# ISP1507.net
KiCad netlist of a schematic drawn in Altium Designer
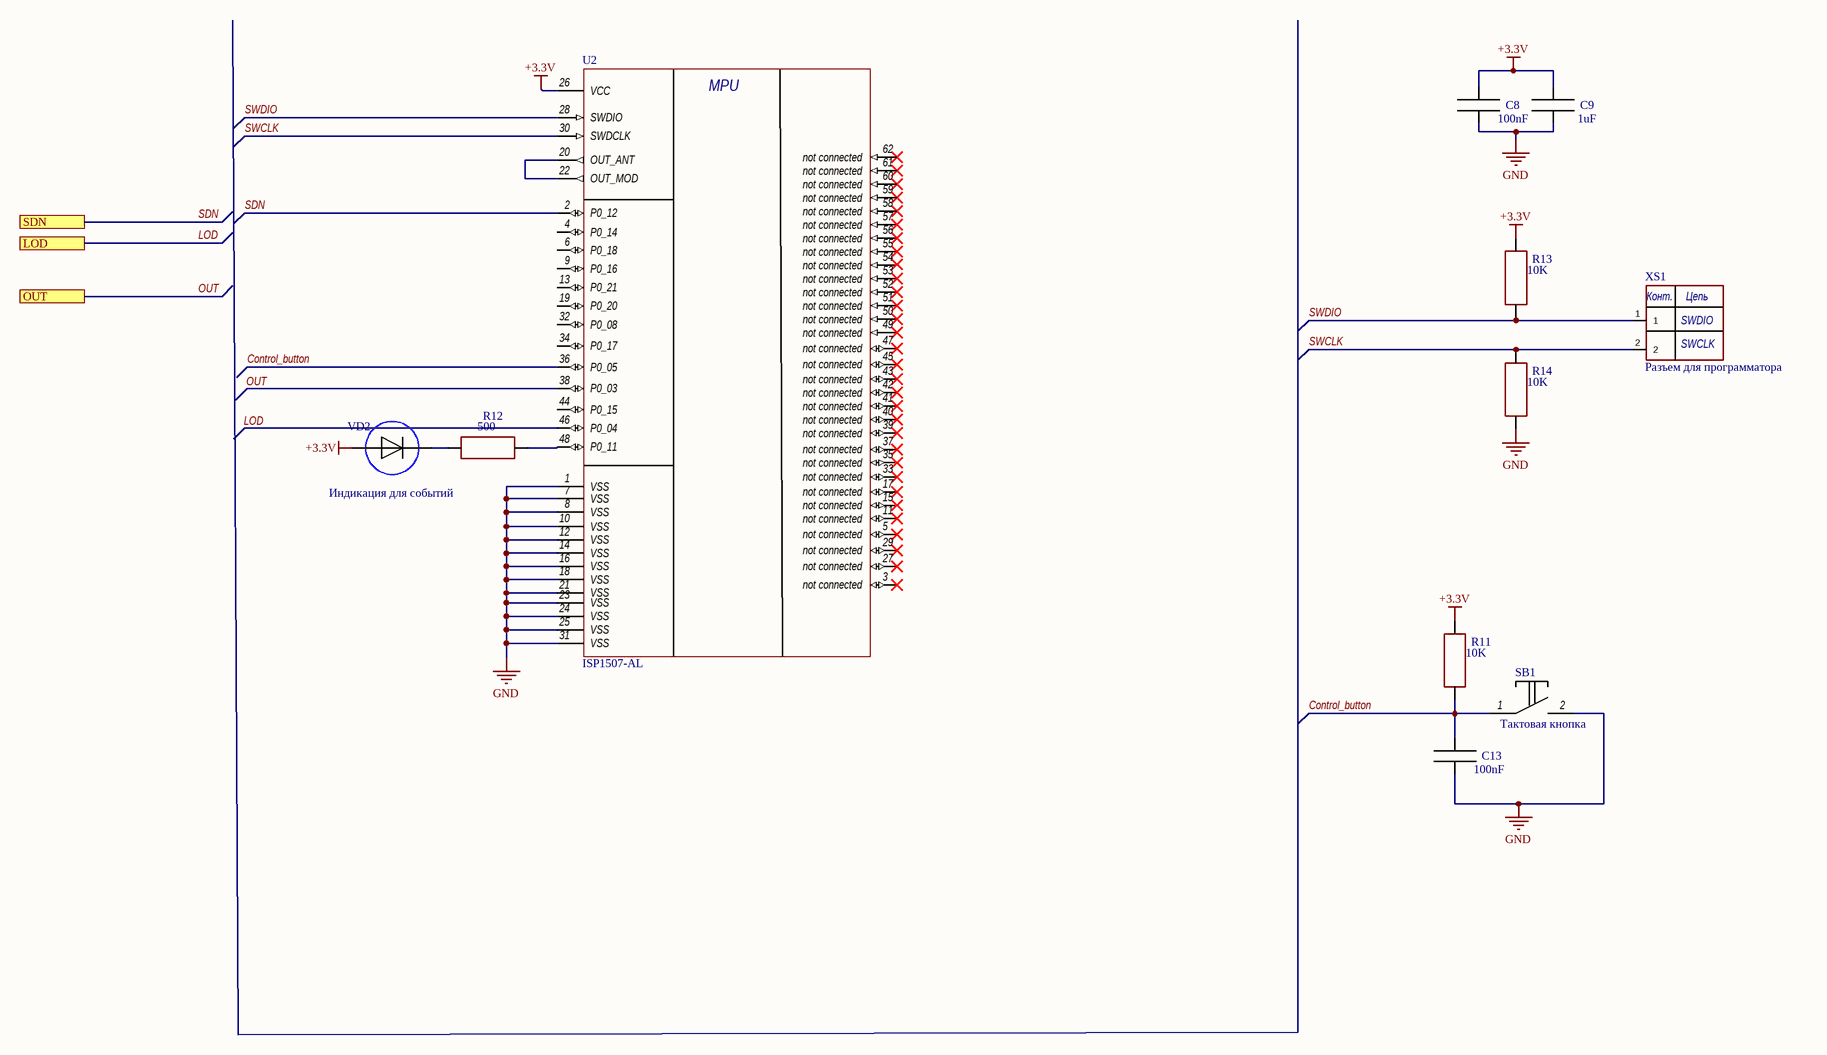
[diagram p0: ISP1507.SchDoc]

(export (version "E")
  (design (tool "Eeschema 10.0.6"))
  (components
    (comp (ref "C8") (value "100nF") (footprint "0402") (libsource (lib "AD8233") (part "Конденсатор")))
    (comp (ref "C9") (value "1uF") (footprint "0402") (libsource (lib "AD8233") (part "Конденсатор")))
    (comp (ref "C13") (value "100nF") (footprint "0402") (libsource (lib "AD8233") (part "Конденсатор")))
    (comp (ref "R11") (value "10K") (footprint "0402") (libsource (lib "AD8233") (part "Резистор")))
    (comp (ref "R12") (value "500") (footprint "0402") (libsource (lib "") (part "Резистор_1")))
    (comp (ref "R13") (value "10K") (footprint "0402") (libsource (lib "AD8233") (part "Резистор")))
    (comp (ref "R14") (value "10K") (footprint "0402") (libsource (lib "AD8233") (part "Резистор")))
    (comp (ref "SB1")
      (value "Тактовая кнопка")
      (footprint "2565")
      (libsource (lib "AD8233") (part "Тактовая кнопка"))
    )
    (comp (ref "U2") (value "ISP1507-AL") (footprint "LGA QFN") (libsource (lib "AD8233") (part "ISP1507")))
    (comp (ref "VD2") (value "Event") (footprint "0402") (libsource (lib "AD8233") (part "Светодиод")))
    (comp (ref "XS1")
      (value "Разъем для программатора")
      (footprint "PIN 2")
      (libsource (lib "AD8233") (part "Разъем 2"))
    )
  )
  (nets
    (net (code "1") (name "+3.3V") (class "Default")
      (node (ref "C8") (pin "2") (pinfunction "2_2") (pintype "passive"))
      (node (ref "C9") (pin "2") (pinfunction "2_2") (pintype "passive"))
      (node (ref "R11") (pin "2") (pinfunction "2_2") (pintype "passive"))
      (node (ref "R13") (pin "2") (pinfunction "2_2") (pintype "passive"))
      (node (ref "U2") (pin "26") (pinfunction "VCC_26") (pintype "power_in"))
      (node (ref "VD2") (pin "1") (pinfunction "1_1") (pintype "passive"))
    )
    (net (code "2") (name "/Control_button") (class "Default")
      (node (ref "C13") (pin "2") (pinfunction "2_2") (pintype "passive"))
      (node (ref "R11") (pin "1") (pinfunction "1_1") (pintype "passive"))
      (node (ref "SB1") (pin "1") (pinfunction "1_1") (pintype "passive"))
      (node (ref "U2") (pin "36") (pinfunction "P0_05_36") (pintype "bidirectional"))
    )
    (net (code "4") (name "/OUT") (class "Default")
      (node (ref "U2") (pin "38") (pinfunction "P0_03_38") (pintype "bidirectional"))
    )
    (net (code "5") (name "/SDN") (class "Default")
      (node (ref "U2") (pin "2") (pinfunction "P0_12_2") (pintype "bidirectional"))
    )
    (net (code "6") (name "/SWCLK") (class "Default")
      (node (ref "R14") (pin "2") (pinfunction "2_2") (pintype "passive"))
      (node (ref "U2") (pin "30") (pinfunction "SWDCLK_30") (pintype "input"))
      (node (ref "XS1") (pin "2") (pinfunction "2_2") (pintype "power_in"))
    )
    (net (code "7") (name "/SWDIO") (class "Default")
      (node (ref "R13") (pin "1") (pinfunction "1_1") (pintype "passive"))
      (node (ref "U2") (pin "28") (pinfunction "SWDIO_28") (pintype "input"))
      (node (ref "XS1") (pin "1") (pinfunction "1_1") (pintype "power_in"))
    )
    (net (code "8") (name "GND") (class "Default")
      (node (ref "C13") (pin "1") (pinfunction "1_1") (pintype "passive"))
      (node (ref "C8") (pin "1") (pinfunction "1_1") (pintype "passive"))
      (node (ref "C9") (pin "1") (pinfunction "1_1") (pintype "passive"))
      (node (ref "R14") (pin "1") (pinfunction "1_1") (pintype "passive"))
      (node (ref "SB1") (pin "2") (pinfunction "2_2") (pintype "passive"))
      (node (ref "U2") (pin "1") (pinfunction "VSS_1") (pintype "power_in"))
      (node (ref "U2") (pin "10") (pinfunction "VSS_10") (pintype "power_in"))
      (node (ref "U2") (pin "12") (pinfunction "VSS_12") (pintype "power_in"))
      (node (ref "U2") (pin "14") (pinfunction "VSS_14") (pintype "power_in"))
      (node (ref "U2") (pin "16") (pinfunction "VSS_16") (pintype "power_in"))
      (node (ref "U2") (pin "18") (pinfunction "VSS_18") (pintype "power_in"))
      (node (ref "U2") (pin "21") (pinfunction "VSS_21") (pintype "power_in"))
      (node (ref "U2") (pin "23") (pinfunction "VSS_23") (pintype "power_in"))
      (node (ref "U2") (pin "24") (pinfunction "VSS_24") (pintype "power_in"))
      (node (ref "U2") (pin "25") (pinfunction "VSS_25") (pintype "power_in"))
      (node (ref "U2") (pin "31") (pinfunction "VSS_31") (pintype "power_in"))
      (node (ref "U2") (pin "7") (pinfunction "VSS_7") (pintype "power_in"))
      (node (ref "U2") (pin "8") (pinfunction "VSS_8") (pintype "power_in"))
    )
    (net (code "9") (name "Net-(R12-Pad2)") (class "Default")
      (node (ref "R12") (pin "2") (pinfunction "2_2") (pintype "passive"))
      (node (ref "VD2") (pin "2") (pinfunction "2_2") (pintype "passive"))
    )
    (net (code "10") (name "Net-(U2-OUT_ANT)") (class "Default")
      (node (ref "U2") (pin "20") (pinfunction "OUT_ANT_20") (pintype "output"))
      (node (ref "U2") (pin "22") (pinfunction "OUT_MOD_22") (pintype "output"))
    )
    (net (code "11") (name "Net-(U2-P0_11)") (class "Default")
      (node (ref "R12") (pin "1") (pinfunction "1_1") (pintype "passive"))
      (node (ref "U2") (pin "48") (pinfunction "P0_11_48") (pintype "bidirectional"))
    )
    (net (code "12") (name "unconnected-(U2-P0_04-Pad46)") (class "Default")
      (node (ref "U2") (pin "46") (pinfunction "P0_04_46") (pintype "bidirectional"))
    )
    (net (code "13") (name "unconnected-(U2-P0_08-Pad32)") (class "Default")
      (node (ref "U2") (pin "32") (pinfunction "P0_08_32") (pintype "bidirectional"))
    )
    (net (code "14") (name "unconnected-(U2-P0_14-Pad4)") (class "Default")
      (node (ref "U2") (pin "4") (pinfunction "P0_14_4") (pintype "bidirectional"))
    )
    (net (code "15") (name "unconnected-(U2-P0_15-Pad44)") (class "Default")
      (node (ref "U2") (pin "44") (pinfunction "P0_15_44") (pintype "bidirectional"))
    )
    (net (code "16") (name "unconnected-(U2-P0_16-Pad9)") (class "Default")
      (node (ref "U2") (pin "9") (pinfunction "P0_16_9") (pintype "bidirectional"))
    )
    (net (code "17") (name "unconnected-(U2-P0_17-Pad34)") (class "Default")
      (node (ref "U2") (pin "34") (pinfunction "P0_17_34") (pintype "bidirectional"))
    )
    (net (code "18") (name "unconnected-(U2-P0_18-Pad6)") (class "Default")
      (node (ref "U2") (pin "6") (pinfunction "P0_18_6") (pintype "bidirectional"))
    )
    (net (code "19") (name "unconnected-(U2-P0_20-Pad19)") (class "Default")
      (node (ref "U2") (pin "19") (pinfunction "P0_20_19") (pintype "bidirectional"))
    )
    (net (code "20") (name "unconnected-(U2-P0_21-Pad13)") (class "Default")
      (node (ref "U2") (pin "13") (pinfunction "P0_21_13") (pintype "bidirectional"))
    )
    (net (code "21") (name "unconnected-(U2-not_connected-Pad3)") (class "Default")
      (node (ref "U2") (pin "3") (pinfunction "not_connected_3") (pintype "bidirectional+no_connect"))
    )
    (net (code "22") (name "unconnected-(U2-not_connected-Pad5)") (class "Default")
      (node (ref "U2") (pin "5") (pinfunction "not_connected_5") (pintype "bidirectional+no_connect"))
    )
    (net (code "23") (name "unconnected-(U2-not_connected-Pad11)") (class "Default")
      (node (ref "U2") (pin "11") (pinfunction "not_connected_11") (pintype "bidirectional+no_connect"))
    )
    (net (code "24") (name "unconnected-(U2-not_connected-Pad15)") (class "Default")
      (node (ref "U2") (pin "15") (pinfunction "not_connected_15") (pintype "bidirectional+no_connect"))
    )
    (net (code "25") (name "unconnected-(U2-not_connected-Pad17)") (class "Default")
      (node (ref "U2") (pin "17") (pinfunction "not_connected_17") (pintype "bidirectional+no_connect"))
    )
    (net (code "26") (name "unconnected-(U2-not_connected-Pad27)") (class "Default")
      (node (ref "U2") (pin "27") (pinfunction "not_connected_27") (pintype "bidirectional+no_connect"))
    )
    (net (code "27") (name "unconnected-(U2-not_connected-Pad29)") (class "Default")
      (node (ref "U2") (pin "29") (pinfunction "not_connected_29") (pintype "bidirectional+no_connect"))
    )
    (net (code "28") (name "unconnected-(U2-not_connected-Pad33)") (class "Default")
      (node (ref "U2") (pin "33") (pinfunction "not_connected_33") (pintype "bidirectional+no_connect"))
    )
    (net (code "29") (name "unconnected-(U2-not_connected-Pad35)") (class "Default")
      (node (ref "U2") (pin "35") (pinfunction "not_connected_35") (pintype "bidirectional+no_connect"))
    )
    (net (code "30") (name "unconnected-(U2-not_connected-Pad37)") (class "Default")
      (node (ref "U2") (pin "37") (pinfunction "not_connected_37") (pintype "bidirectional+no_connect"))
    )
    (net (code "31") (name "unconnected-(U2-not_connected-Pad39)") (class "Default")
      (node (ref "U2") (pin "39") (pinfunction "not_connected_39") (pintype "bidirectional+no_connect"))
    )
    (net (code "32") (name "unconnected-(U2-not_connected-Pad40)") (class "Default")
      (node (ref "U2") (pin "40") (pinfunction "not_connected_40") (pintype "bidirectional+no_connect"))
    )
    (net (code "33") (name "unconnected-(U2-not_connected-Pad41)") (class "Default")
      (node (ref "U2") (pin "41") (pinfunction "not_connected_41") (pintype "bidirectional+no_connect"))
    )
    (net (code "34") (name "unconnected-(U2-not_connected-Pad42)") (class "Default")
      (node (ref "U2") (pin "42") (pinfunction "not_connected_42") (pintype "bidirectional+no_connect"))
    )
    (net (code "35") (name "unconnected-(U2-not_connected-Pad43)") (class "Default")
      (node (ref "U2") (pin "43") (pinfunction "not_connected_43") (pintype "bidirectional+no_connect"))
    )
    (net (code "36") (name "unconnected-(U2-not_connected-Pad45)") (class "Default")
      (node (ref "U2") (pin "45") (pinfunction "not_connected_45") (pintype "bidirectional+no_connect"))
    )
    (net (code "37") (name "unconnected-(U2-not_connected-Pad47)") (class "Default")
      (node (ref "U2") (pin "47") (pinfunction "not_connected_47") (pintype "bidirectional+no_connect"))
    )
    (net (code "38") (name "unconnected-(U2-not_connected-Pad49)") (class "Default")
      (node (ref "U2") (pin "49") (pinfunction "not_connected_49") (pintype "input+no_connect"))
    )
    (net (code "39") (name "unconnected-(U2-not_connected-Pad50)") (class "Default")
      (node (ref "U2") (pin "50") (pinfunction "not_connected_50") (pintype "input+no_connect"))
    )
    (net (code "40") (name "unconnected-(U2-not_connected-Pad51)") (class "Default")
      (node (ref "U2") (pin "51") (pinfunction "not_connected_51") (pintype "input+no_connect"))
    )
    (net (code "41") (name "unconnected-(U2-not_connected-Pad52)") (class "Default")
      (node (ref "U2") (pin "52") (pinfunction "not_connected_52") (pintype "input+no_connect"))
    )
    (net (code "42") (name "unconnected-(U2-not_connected-Pad53)") (class "Default")
      (node (ref "U2") (pin "53") (pinfunction "not_connected_53") (pintype "input+no_connect"))
    )
    (net (code "43") (name "unconnected-(U2-not_connected-Pad54)") (class "Default")
      (node (ref "U2") (pin "54") (pinfunction "not_connected_54") (pintype "input"))
    )
    (net (code "44") (name "unconnected-(U2-not_connected-Pad55)") (class "Default")
      (node (ref "U2") (pin "55") (pinfunction "not_connected_55") (pintype "input+no_connect"))
    )
    (net (code "45") (name "unconnected-(U2-not_connected-Pad56)") (class "Default")
      (node (ref "U2") (pin "56") (pinfunction "not_connected_56") (pintype "input+no_connect"))
    )
    (net (code "46") (name "unconnected-(U2-not_connected-Pad57)") (class "Default")
      (node (ref "U2") (pin "57") (pinfunction "not_connected_57") (pintype "input+no_connect"))
    )
    (net (code "47") (name "unconnected-(U2-not_connected-Pad58)") (class "Default")
      (node (ref "U2") (pin "58") (pinfunction "not_connected_58") (pintype "input+no_connect"))
    )
    (net (code "48") (name "unconnected-(U2-not_connected-Pad59)") (class "Default")
      (node (ref "U2") (pin "59") (pinfunction "not_connected_59") (pintype "input+no_connect"))
    )
    (net (code "49") (name "unconnected-(U2-not_connected-Pad60)") (class "Default")
      (node (ref "U2") (pin "60") (pinfunction "not_connected_60") (pintype "input+no_connect"))
    )
    (net (code "50") (name "unconnected-(U2-not_connected-Pad61)") (class "Default")
      (node (ref "U2") (pin "61") (pinfunction "not_connected_61") (pintype "input+no_connect"))
    )
    (net (code "51") (name "unconnected-(U2-not_connected-Pad62)") (class "Default")
      (node (ref "U2") (pin "62") (pinfunction "not_connected_62") (pintype "input+no_connect"))
    )
  )
)
